# I2C.net
KiCad netlist of a schematic drawn in EAGLE
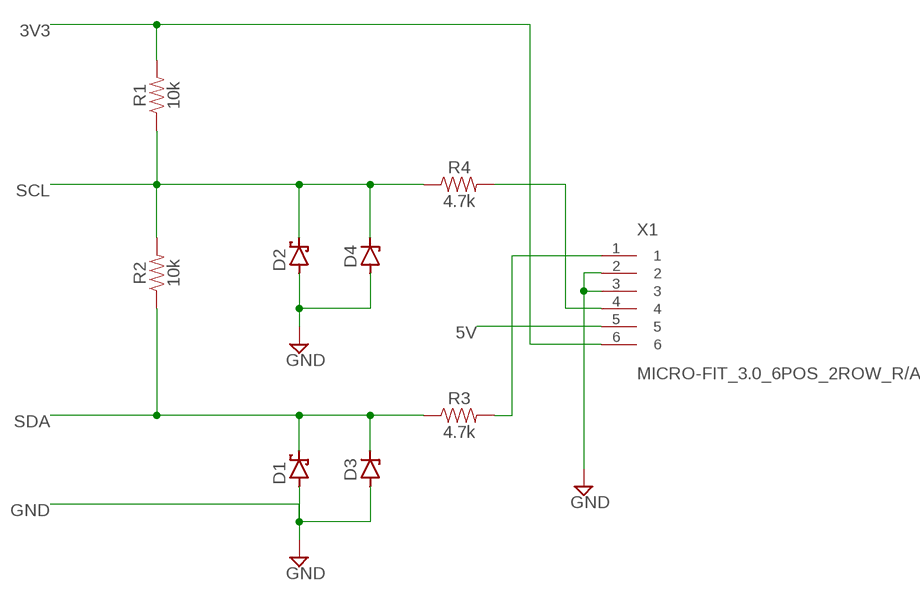
[diagram p0: schematic, sheet 1]

(export (version "E")
  (design (tool "Eeschema 10.0.6"))
  (components
    (comp (ref "D1")
      (value "SCHOTTKY-DIODESMD")
      (footprint "eagle-import:SMB")
      (libsource (lib "eagle-import") (part "SCHOTTKY-DIODESMD"))
    )
    (comp (ref "D2")
      (value "SCHOTTKY-DIODESMD")
      (footprint "eagle-import:SMB")
      (libsource (lib "eagle-import") (part "SCHOTTKY-DIODESMD"))
    )
    (comp (ref "D3")
      (value "ZENER-DIODESOT23")
      (footprint "eagle-import:SOT23")
      (libsource (lib "eagle-import") (part "ZENER-DIODESOT23"))
    )
    (comp (ref "D4")
      (value "ZENER-DIODESOT23")
      (footprint "eagle-import:SOT23")
      (libsource (lib "eagle-import") (part "ZENER-DIODESOT23"))
    )
    (comp (ref "R1")
      (value "10k")
      (footprint "eagle-import:R0603")
      (fields (field (name "MANUFACTURER") "Panasonic"))
      (libsource (lib "eagle-import") (part "RES-10KOHM-0603-1/10W-1%"))
    )
    (comp (ref "R2")
      (value "10k")
      (footprint "eagle-import:R0603")
      (fields (field (name "MANUFACTURER") "Panasonic"))
      (libsource (lib "eagle-import") (part "RES-10KOHM-0603-1/10W-1%"))
    )
    (comp (ref "R3")
      (value "4.7k")
      (footprint "eagle-import:R0603")
      (fields (field (name "MANUFACTURER") "Panasonic Electronic Components"))
      (libsource (lib "eagle-import") (part "RES-4.7KOHM-0603-1/10W-1%"))
    )
    (comp (ref "R4")
      (value "4.7k")
      (footprint "eagle-import:R0603")
      (fields (field (name "MANUFACTURER") "Panasonic Electronic Components"))
      (libsource (lib "eagle-import") (part "RES-4.7KOHM-0603-1/10W-1%"))
    )
    (comp (ref "X1")
      (value "MICRO-FIT_3.0_6POS_2ROW_R/A")
      (footprint "eagle-import:0430450600")
      (fields (field (name "MANUFACTURER") "Molex"))
      (libsource (lib "eagle-import") (part "MICRO-FIT_3.0_6POS_2ROW_R/A"))
    )
  )
  (nets
    (net (code "1") (name "/3V3") (class "Default")
      (node (ref "R1") (pin "2") (pinfunction "2_2") (pintype "passive"))
      (node (ref "X1") (pin "6") (pinfunction "6_6") (pintype "bidirectional"))
    )
    (net (code "2") (name "/5V") (class "Default")
      (node (ref "X1") (pin "5") (pinfunction "5_5") (pintype "bidirectional"))
    )
    (net (code "3") (name "/SCL") (class "Default")
      (node (ref "D2") (pin "C") (pinfunction "C_C") (pintype "passive"))
      (node (ref "D4") (pin "3") (pinfunction "C_3") (pintype "passive"))
      (node (ref "R1") (pin "1") (pinfunction "1_1") (pintype "passive"))
      (node (ref "R2") (pin "2") (pinfunction "2_2") (pintype "passive"))
      (node (ref "R4") (pin "1") (pinfunction "1_1") (pintype "passive"))
    )
    (net (code "4") (name "/SDA") (class "Default")
      (node (ref "D1") (pin "C") (pinfunction "C_C") (pintype "passive"))
      (node (ref "D3") (pin "3") (pinfunction "C_3") (pintype "passive"))
      (node (ref "R2") (pin "1") (pinfunction "1_1") (pintype "passive"))
      (node (ref "R3") (pin "1") (pinfunction "1_1") (pintype "passive"))
    )
    (net (code "5") (name "GND") (class "Default")
      (node (ref "D1") (pin "A") (pinfunction "A_A") (pintype "passive"))
      (node (ref "D2") (pin "A") (pinfunction "A_A") (pintype "passive"))
      (node (ref "D3") (pin "1") (pinfunction "A_1") (pintype "passive"))
      (node (ref "D4") (pin "1") (pinfunction "A_1") (pintype "passive"))
      (node (ref "X1") (pin "2") (pinfunction "2_2") (pintype "bidirectional"))
      (node (ref "X1") (pin "3") (pinfunction "3_3") (pintype "bidirectional"))
    )
    (net (code "6") (name "Net-(R3-Pad2)") (class "Default")
      (node (ref "R3") (pin "2") (pinfunction "2_2") (pintype "passive"))
      (node (ref "X1") (pin "1") (pinfunction "1_1") (pintype "bidirectional"))
    )
    (net (code "7") (name "Net-(R4-Pad2)") (class "Default")
      (node (ref "R4") (pin "2") (pinfunction "2_2") (pintype "passive"))
      (node (ref "X1") (pin "4") (pinfunction "4_4") (pintype "bidirectional"))
    )
  )
)
